# Analog_Input.net
KiCad netlist of a schematic drawn in Altium Designer
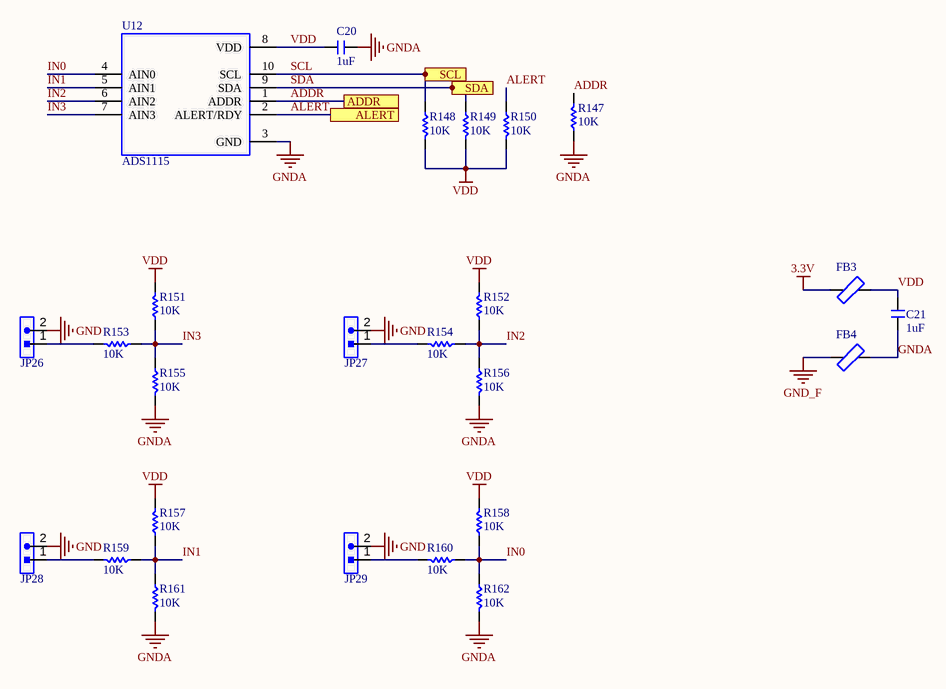
[diagram p0: Analog Input.SchDoc]

(export (version "E")
  (design (tool "Eeschema 10.0.6"))
  (components
    (comp (ref "C20")
      (value "1uF")
      (footprint "C 0805")
      (description "Non-polar patch capacitor")
      (fields (field (name "版权归属") "源创客"))
      (libsource (lib "Passive (Resistor-Capacitor-Inductor-Veristor-Ferrite)") (part "C"))
    )
    (comp (ref "C21")
      (value "1uF")
      (footprint "C 0805")
      (description "Non-polar patch capacitor")
      (fields (field (name "版权归属") "源创客"))
      (libsource (lib "Passive (Resistor-Capacitor-Inductor-Veristor-Ferrite)") (part "C"))
    )
    (comp (ref "FB3")
      (value "~")
      (footprint "F 0805")
      (description "Ferrite Bead")
      (fields (field (name "版权归属") "源创客"))
      (libsource (lib "Passive (Resistor-Capacitor-Inductor-Veristor-Ferrite)") (part "FB"))
    )
    (comp (ref "FB4")
      (value "~")
      (footprint "F 0805")
      (description "Ferrite Bead")
      (fields (field (name "版权归属") "源创客"))
      (libsource (lib "Passive (Resistor-Capacitor-Inductor-Veristor-Ferrite)") (part "FB"))
    )
    (comp (ref "JP26")
      (value "HDR-1X2")
      (footprint "KF301-2P")
      (description "2P Connector")
      (fields (field (name "版权归属") "源创客"))
      (libsource (lib "Connectors") (part "Header 2"))
    )
    (comp (ref "JP27")
      (value "HDR-1X2")
      (footprint "KF301-2P")
      (description "2P Connector")
      (fields (field (name "版权归属") "源创客"))
      (libsource (lib "Connectors") (part "Header 2"))
    )
    (comp (ref "JP28")
      (value "HDR-1X2")
      (footprint "KF301-2P")
      (description "2P Connector")
      (fields (field (name "版权归属") "源创客"))
      (libsource (lib "Connectors") (part "Header 2"))
    )
    (comp (ref "JP29")
      (value "HDR-1X2")
      (footprint "KF301-2P")
      (description "2P Connector")
      (fields (field (name "版权归属") "源创客"))
      (libsource (lib "Connectors") (part "Header 2"))
    )
    (comp (ref "R147")
      (value "10K")
      (footprint "R 0805")
      (description "Chip resistor")
      (fields (field (name "版权归属") "源创客"))
      (libsource (lib "Passive (Resistor-Capacitor-Inductor-Veristor-Ferrite)") (part "R"))
    )
    (comp (ref "R148")
      (value "10K")
      (footprint "R 0805")
      (description "Chip resistor")
      (fields (field (name "版权归属") "源创客"))
      (libsource (lib "Passive (Resistor-Capacitor-Inductor-Veristor-Ferrite)") (part "R"))
    )
    (comp (ref "R149")
      (value "10K")
      (footprint "R 0805")
      (description "Chip resistor")
      (fields (field (name "版权归属") "源创客"))
      (libsource (lib "Passive (Resistor-Capacitor-Inductor-Veristor-Ferrite)") (part "R"))
    )
    (comp (ref "R150")
      (value "10K")
      (footprint "R 0805")
      (description "Chip resistor")
      (fields (field (name "版权归属") "源创客"))
      (libsource (lib "Passive (Resistor-Capacitor-Inductor-Veristor-Ferrite)") (part "R"))
    )
    (comp (ref "R151")
      (value "10K")
      (footprint "R 0805")
      (description "Chip resistor")
      (fields (field (name "版权归属") "源创客"))
      (libsource (lib "Passive (Resistor-Capacitor-Inductor-Veristor-Ferrite)") (part "R"))
    )
    (comp (ref "R152")
      (value "10K")
      (footprint "R 0805")
      (description "Chip resistor")
      (fields (field (name "版权归属") "源创客"))
      (libsource (lib "Passive (Resistor-Capacitor-Inductor-Veristor-Ferrite)") (part "R"))
    )
    (comp (ref "R153")
      (value "10K")
      (footprint "R 0805")
      (description "Chip resistor")
      (fields (field (name "版权归属") "源创客"))
      (libsource (lib "Passive (Resistor-Capacitor-Inductor-Veristor-Ferrite)") (part "R"))
    )
    (comp (ref "R154")
      (value "10K")
      (footprint "R 0805")
      (description "Chip resistor")
      (fields (field (name "版权归属") "源创客"))
      (libsource (lib "Passive (Resistor-Capacitor-Inductor-Veristor-Ferrite)") (part "R"))
    )
    (comp (ref "R155")
      (value "10K")
      (footprint "R 0805")
      (description "Chip resistor")
      (fields (field (name "版权归属") "源创客"))
      (libsource (lib "Passive (Resistor-Capacitor-Inductor-Veristor-Ferrite)") (part "R"))
    )
    (comp (ref "R156")
      (value "10K")
      (footprint "R 0805")
      (description "Chip resistor")
      (fields (field (name "版权归属") "源创客"))
      (libsource (lib "Passive (Resistor-Capacitor-Inductor-Veristor-Ferrite)") (part "R"))
    )
    (comp (ref "R157")
      (value "10K")
      (footprint "R 0805")
      (description "Chip resistor")
      (fields (field (name "版权归属") "源创客"))
      (libsource (lib "Passive (Resistor-Capacitor-Inductor-Veristor-Ferrite)") (part "R"))
    )
    (comp (ref "R158")
      (value "10K")
      (footprint "R 0805")
      (description "Chip resistor")
      (fields (field (name "版权归属") "源创客"))
      (libsource (lib "Passive (Resistor-Capacitor-Inductor-Veristor-Ferrite)") (part "R"))
    )
    (comp (ref "R159")
      (value "10K")
      (footprint "R 0805")
      (description "Chip resistor")
      (fields (field (name "版权归属") "源创客"))
      (libsource (lib "Passive (Resistor-Capacitor-Inductor-Veristor-Ferrite)") (part "R"))
    )
    (comp (ref "R160")
      (value "10K")
      (footprint "R 0805")
      (description "Chip resistor")
      (fields (field (name "版权归属") "源创客"))
      (libsource (lib "Passive (Resistor-Capacitor-Inductor-Veristor-Ferrite)") (part "R"))
    )
    (comp (ref "R161")
      (value "10K")
      (footprint "R 0805")
      (description "Chip resistor")
      (fields (field (name "版权归属") "源创客"))
      (libsource (lib "Passive (Resistor-Capacitor-Inductor-Veristor-Ferrite)") (part "R"))
    )
    (comp (ref "R162")
      (value "10K")
      (footprint "R 0805")
      (description "Chip resistor")
      (fields (field (name "版权归属") "源创客"))
      (libsource (lib "Passive (Resistor-Capacitor-Inductor-Veristor-Ferrite)") (part "R"))
    )
    (comp (ref "U12")
      (value "ADS1115")
      (footprint "VSSOP10-N")
      (fields (field (name "版权归属") "源创客"))
      (libsource (lib "Integrated Circuit") (part "ADS1115"))
    )
  )
  (nets
    (net (code "1") (name "/ADDR") (class "Default")
      (node (ref "R147") (pin "2") (pinfunction "2_2") (pintype "passive"))
      (node (ref "U12") (pin "1") (pinfunction "ADDR_1") (pintype "passive"))
    )
    (net (code "2") (name "/ALERT") (class "Default")
      (node (ref "R150") (pin "1") (pinfunction "1_1") (pintype "passive"))
      (node (ref "U12") (pin "2") (pinfunction "ALERT/RDY_2") (pintype "passive"))
    )
    (net (code "3") (name "/IN0") (class "Default")
      (node (ref "R158") (pin "1") (pinfunction "1_1") (pintype "passive"))
      (node (ref "R160") (pin "1") (pinfunction "1_1") (pintype "passive"))
      (node (ref "R162") (pin "1") (pinfunction "1_1") (pintype "passive"))
      (node (ref "U12") (pin "4") (pinfunction "AIN0_4") (pintype "passive"))
    )
    (net (code "4") (name "/IN1") (class "Default")
      (node (ref "R157") (pin "1") (pinfunction "1_1") (pintype "passive"))
      (node (ref "R159") (pin "1") (pinfunction "1_1") (pintype "passive"))
      (node (ref "R161") (pin "1") (pinfunction "1_1") (pintype "passive"))
      (node (ref "U12") (pin "5") (pinfunction "AIN1_5") (pintype "passive"))
    )
    (net (code "5") (name "/IN2") (class "Default")
      (node (ref "R152") (pin "1") (pinfunction "1_1") (pintype "passive"))
      (node (ref "R154") (pin "1") (pinfunction "1_1") (pintype "passive"))
      (node (ref "R156") (pin "1") (pinfunction "1_1") (pintype "passive"))
      (node (ref "U12") (pin "6") (pinfunction "AIN2_6") (pintype "passive"))
    )
    (net (code "6") (name "/IN3") (class "Default")
      (node (ref "R151") (pin "1") (pinfunction "1_1") (pintype "passive"))
      (node (ref "R153") (pin "1") (pinfunction "1_1") (pintype "passive"))
      (node (ref "R155") (pin "1") (pinfunction "1_1") (pintype "passive"))
      (node (ref "U12") (pin "7") (pinfunction "AIN3_7") (pintype "passive"))
    )
    (net (code "7") (name "/SCL") (class "Default")
      (node (ref "R148") (pin "1") (pinfunction "1_1") (pintype "passive"))
      (node (ref "U12") (pin "10") (pinfunction "SCL_10") (pintype "passive"))
    )
    (net (code "8") (name "/SDA") (class "Default")
      (node (ref "R149") (pin "1") (pinfunction "1_1") (pintype "passive"))
      (node (ref "U12") (pin "9") (pinfunction "SDA_9") (pintype "passive"))
    )
    (net (code "9") (name "3.3V") (class "Default")
      (node (ref "FB3") (pin "1") (pinfunction "1_1") (pintype "passive"))
    )
    (net (code "10") (name "GND") (class "Default")
      (node (ref "JP26") (pin "2") (pintype "passive"))
      (node (ref "JP27") (pin "2") (pintype "passive"))
      (node (ref "JP28") (pin "2") (pintype "passive"))
      (node (ref "JP29") (pin "2") (pintype "passive"))
    )
    (net (code "11") (name "GNDA") (class "Default")
      (node (ref "C20") (pin "1") (pinfunction "1_1") (pintype "passive"))
      (node (ref "C21") (pin "1") (pinfunction "1_1") (pintype "passive"))
      (node (ref "FB4") (pin "2") (pinfunction "2_2") (pintype "passive"))
      (node (ref "R147") (pin "1") (pinfunction "1_1") (pintype "passive"))
      (node (ref "R155") (pin "2") (pinfunction "2_2") (pintype "passive"))
      (node (ref "R156") (pin "2") (pinfunction "2_2") (pintype "passive"))
      (node (ref "R161") (pin "2") (pinfunction "2_2") (pintype "passive"))
      (node (ref "R162") (pin "2") (pinfunction "2_2") (pintype "passive"))
      (node (ref "U12") (pin "3") (pinfunction "GND_3") (pintype "passive"))
    )
    (net (code "12") (name "GND_F") (class "Default")
      (node (ref "FB4") (pin "1") (pinfunction "1_1") (pintype "passive"))
    )
    (net (code "13") (name "Net-(JP26-Pad1)") (class "Default")
      (node (ref "JP26") (pin "1") (pintype "passive"))
      (node (ref "R153") (pin "2") (pinfunction "2_2") (pintype "passive"))
    )
    (net (code "14") (name "Net-(JP27-Pad1)") (class "Default")
      (node (ref "JP27") (pin "1") (pintype "passive"))
      (node (ref "R154") (pin "2") (pinfunction "2_2") (pintype "passive"))
    )
    (net (code "15") (name "Net-(JP28-Pad1)") (class "Default")
      (node (ref "JP28") (pin "1") (pintype "passive"))
      (node (ref "R159") (pin "2") (pinfunction "2_2") (pintype "passive"))
    )
    (net (code "16") (name "Net-(JP29-Pad1)") (class "Default")
      (node (ref "JP29") (pin "1") (pintype "passive"))
      (node (ref "R160") (pin "2") (pinfunction "2_2") (pintype "passive"))
    )
    (net (code "17") (name "VDD") (class "Default")
      (node (ref "C20") (pin "2") (pinfunction "2_2") (pintype "passive"))
      (node (ref "C21") (pin "2") (pinfunction "2_2") (pintype "passive"))
      (node (ref "FB3") (pin "2") (pinfunction "2_2") (pintype "passive"))
      (node (ref "R148") (pin "2") (pinfunction "2_2") (pintype "passive"))
      (node (ref "R149") (pin "2") (pinfunction "2_2") (pintype "passive"))
      (node (ref "R150") (pin "2") (pinfunction "2_2") (pintype "passive"))
      (node (ref "R151") (pin "2") (pinfunction "2_2") (pintype "passive"))
      (node (ref "R152") (pin "2") (pinfunction "2_2") (pintype "passive"))
      (node (ref "R157") (pin "2") (pinfunction "2_2") (pintype "passive"))
      (node (ref "R158") (pin "2") (pinfunction "2_2") (pintype "passive"))
      (node (ref "U12") (pin "8") (pinfunction "VDD_8") (pintype "passive"))
    )
  )
)
